# Sheet1.net
KiCad netlist of a schematic drawn in Altium Designer
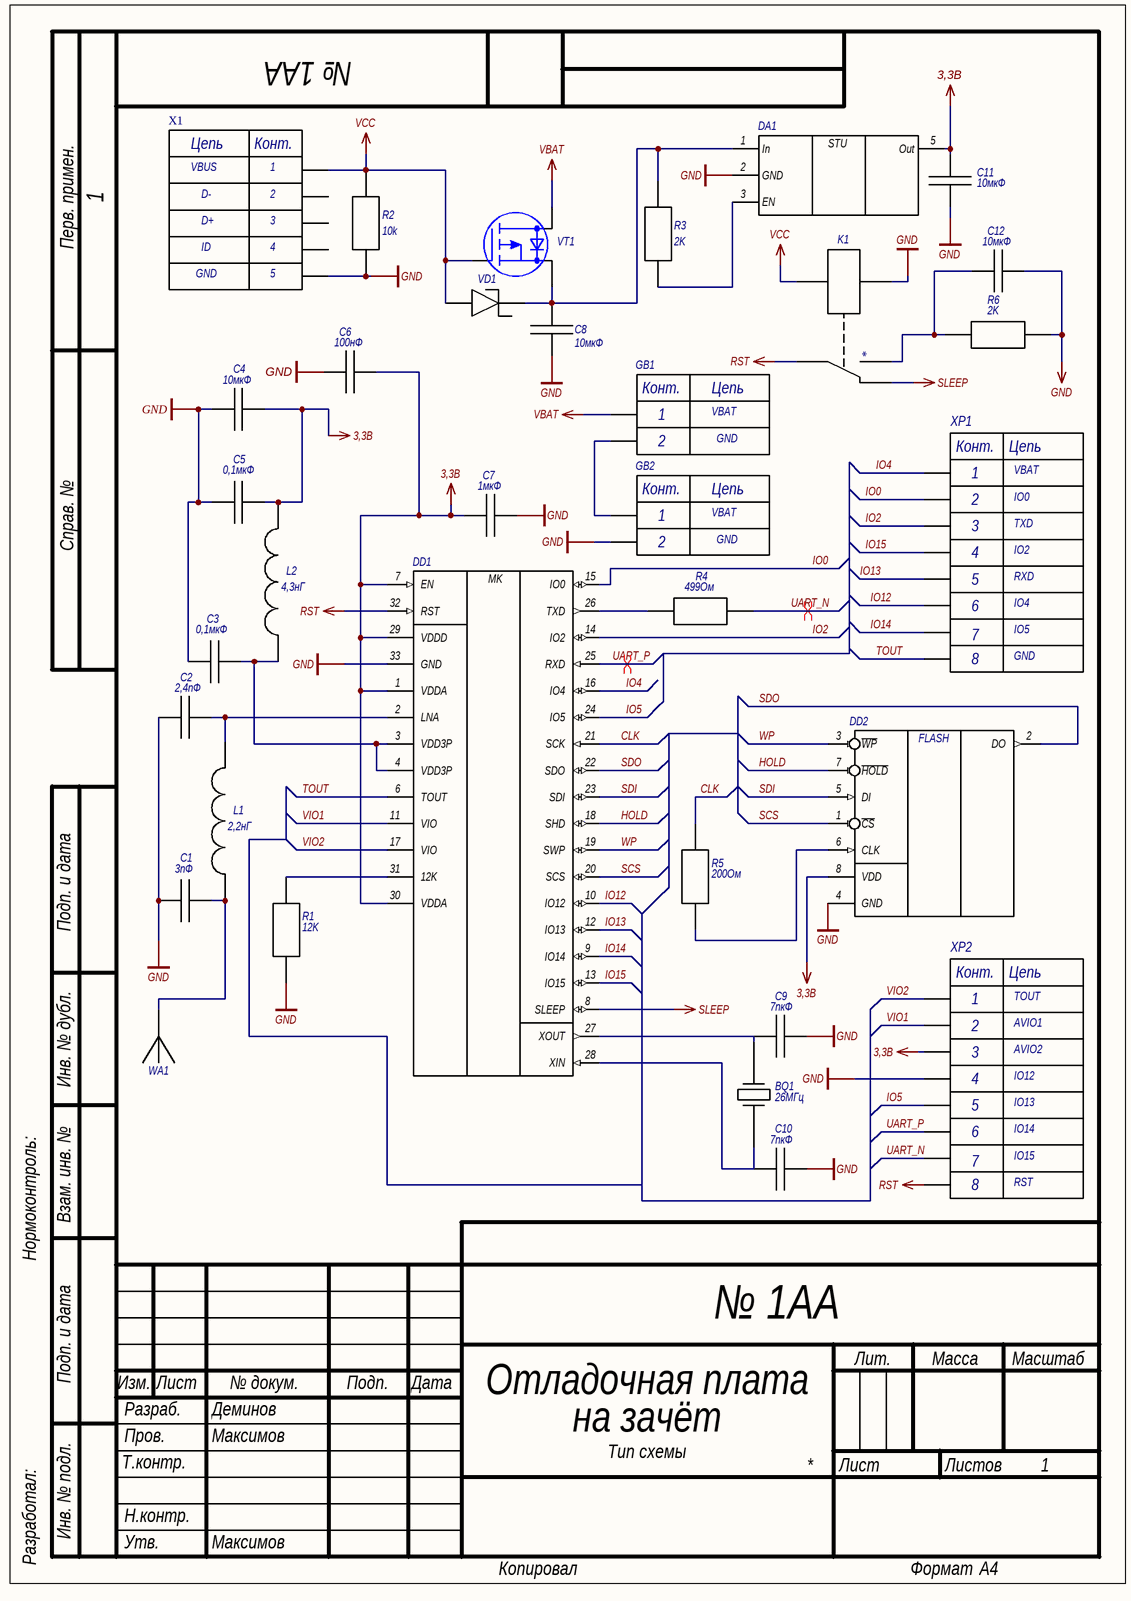
[diagram p0: Sheet1.SchDoc]

(export (version "E")
  (design (tool "Eeschema 10.0.6"))
  (components
    (comp (ref "*") (value "WA1") (libsource (lib "my_lib") (part "ANT GOST")))
    (comp (ref "BQ1")
      (value "26МГц")
      (footprint "SMD02520C4")
      (libsource (lib "my_lib") (part "LBY001XRA001"))
    )
    (comp (ref "C1")
      (value "3пФ")
      (footprint "0201 C0G 7пФ 25В")
      (libsource (lib "my_lib") (part "0201 cap"))
    )
    (comp (ref "C2")
      (value "2,4пФ")
      (footprint "0201 C0G 7пФ 25В")
      (libsource (lib "my_lib") (part "0201 cap"))
    )
    (comp (ref "C3")
      (value "0,1мкФ")
      (footprint "RES 0402")
      (libsource (lib "my_lib") (part "GRM152C80G104KE19D"))
    )
    (comp (ref "C4")
      (value "10мкФ")
      (footprint "FB 0603")
      (libsource (lib "my_lib") (part "GRM188R60G106ME47D"))
    )
    (comp (ref "C5")
      (value "0,1мкФ")
      (footprint "RES 0402")
      (libsource (lib "my_lib") (part "GRM152C80G104KE19D"))
    )
    (comp (ref "C6")
      (value "100нФ")
      (footprint "RES 0402")
      (libsource (lib "my_lib") (part "GRM152C80G104KE19D"))
    )
    (comp (ref "C7")
      (value "1мкФ")
      (footprint "FB 0603")
      (libsource (lib "my_lib") (part "CC0603KRX7R5BB105 1мкФ"))
    )
    (comp (ref "C8")
      (value "10мкФ")
      (footprint "FB 0603")
      (libsource (lib "my_lib") (part "GRM188R60G106ME47D"))
    )
    (comp (ref "C9")
      (value "7пкФ")
      (footprint "0201 C0G 7пФ 25В")
      (libsource (lib "my_lib") (part "0201 cap"))
    )
    (comp (ref "C10")
      (value "7пкФ")
      (footprint "0201 C0G 7пФ 25В")
      (libsource (lib "my_lib") (part "0201 cap"))
    )
    (comp (ref "C11")
      (value "10мкФ")
      (footprint "FB 0603")
      (libsource (lib "my_lib") (part "GRM188R60G106ME47D"))
    )
    (comp (ref "C12")
      (value "10мкФ")
      (footprint "FB 0603")
      (libsource (lib "my_lib") (part "GRM188R60G106ME47D"))
    )
    (comp (ref "DA1") (value "ap2112") (footprint "2112") (libsource (lib "my_lib") (part "ap2112")))
    (comp (ref "DD1") (value "esp8266ex") (footprint "ESP8266") (libsource (lib "my_lib") (part "esp8266ex")))
    (comp (ref "DD2")
      (value "M25P16-VMN6TP")
      (footprint "SOIC-8(3.90мм)")
      (libsource (lib "my_lib") (part "M25P16-VMN6TP"))
    )
    (comp (ref "GB1")
      (value "battery_x2")
      (footprint "Battery_x2AA")
      (libsource (lib "my_lib") (part "battery_x2"))
    )
    (comp (ref "GB2")
      (value "battery_x2")
      (footprint "Battery_x2AA")
      (libsource (lib "my_lib") (part "battery_x2"))
    )
    (comp (ref "K1") (value "gost relay") (footprint "RELE") (libsource (lib "my_lib") (part "gost relay")))
    (comp (ref "L1") (value "2,2нГ") (footprint "FB 0603") (libsource (lib "my_lib") (part "LQW18AN2N2D")))
    (comp (ref "L2")
      (value "4,3нГ")
      (footprint "RES 0402")
      (libsource (lib "my_lib") (part "LQP15MN4N3B02D"))
    )
    (comp (ref "R1") (value "12K") (footprint "RES 0805") (libsource (lib "my_lib") (part "RES 0805")))
    (comp (ref "R2") (value "10k") (footprint "RES 0805") (libsource (lib "my_lib") (part "RES 0805")))
    (comp (ref "R3") (value "2K") (footprint "RES 0805") (libsource (lib "my_lib") (part "RES 0805")))
    (comp (ref "R4") (value "499Ом") (footprint "RES 0805") (libsource (lib "my_lib") (part "RES 0805")))
    (comp (ref "R5") (value "200Ом") (footprint "RES 0805") (libsource (lib "my_lib") (part "RES 0805")))
    (comp (ref "R6") (value "2K") (footprint "RES 0805") (libsource (lib "my_lib") (part "RES 0805")))
    (comp (ref "VD1") (value "~") (footprint "MBR120") (libsource (lib "my_lib") (part "MBR120")))
    (comp (ref "VT1")
      (value "~")
      (footprint "SOT23-3")
      (description "N-MOSFET")
      (fields (field (name "PART NUMBER") "SI2325DS-T1-GE3") (field (name "MANUFACTURER") "IXYS"))
      (libsource (lib "MOP44") (part "P-MOSFET"))
    )
    (comp (ref "X1")
      (value "usb_micro")
      (footprint "USB_mini_B")
      (libsource (lib "my_lib") (part "usb_micro"))
    )
    (comp (ref "XP1")
      (value "PLD-8")
      (footprint "PLD-8")
      (description "PLD connector")
      (fields (field (name "MANUFACTURER") "NONAME"))
      (libsource (lib "my_lib") (part "PLD-8"))
    )
    (comp (ref "XP2")
      (value "PLD-8")
      (footprint "PLD-8")
      (description "PLD connector")
      (fields (field (name "MANUFACTURER") "NONAME"))
      (libsource (lib "my_lib") (part "PLD-8"))
    )
  )
  (nets
    (net (code "1") (name "/CLK") (class "Default")
      (node (ref "DD1") (pin "21") (pinfunction "SCK_21") (pintype "input"))
      (node (ref "R5") (pin "1") (pinfunction "1_1") (pintype "passive"))
    )
    (net (code "2") (name "/HOLD") (class "Default")
      (node (ref "DD1") (pin "18") (pinfunction "SHD_18") (pintype "bidirectional"))
      (node (ref "DD2") (pin "7") (pinfunction "~{HOLD}_7") (pintype "input"))
    )
    (net (code "3") (name "/IO0") (class "Default")
      (node (ref "DD1") (pin "15") (pinfunction "IO0_15") (pintype "bidirectional"))
      (node (ref "XP1") (pin "2") (pinfunction "2_2") (pintype "passive"))
    )
    (net (code "4") (name "/IO2") (class "Default")
      (node (ref "DD1") (pin "14") (pinfunction "IO2_14") (pintype "bidirectional"))
      (node (ref "XP1") (pin "3") (pinfunction "3_3") (pintype "passive"))
    )
    (net (code "5") (name "/IO4") (class "Default")
      (node (ref "DD1") (pin "16") (pinfunction "IO4_16") (pintype "bidirectional"))
      (node (ref "XP1") (pin "1") (pinfunction "1_1") (pintype "passive"))
    )
    (net (code "6") (name "/IO5") (class "Default")
      (node (ref "DD1") (pin "24") (pinfunction "IO5_24") (pintype "bidirectional"))
      (node (ref "XP2") (pin "5") (pinfunction "5_5") (pintype "passive"))
    )
    (net (code "7") (name "/IO12") (class "Default")
      (node (ref "DD1") (pin "10") (pinfunction "IO12_10") (pintype "bidirectional"))
      (node (ref "XP1") (pin "6") (pinfunction "6_6") (pintype "passive"))
    )
    (net (code "8") (name "/IO13") (class "Default")
      (node (ref "DD1") (pin "12") (pinfunction "IO13_12") (pintype "bidirectional"))
      (node (ref "XP1") (pin "5") (pinfunction "5_5") (pintype "passive"))
    )
    (net (code "9") (name "/IO14") (class "Default")
      (node (ref "DD1") (pin "9") (pinfunction "IO14_9") (pintype "bidirectional"))
      (node (ref "XP1") (pin "7") (pinfunction "7_7") (pintype "passive"))
    )
    (net (code "10") (name "/IO15") (class "Default")
      (node (ref "DD1") (pin "13") (pinfunction "IO15_13") (pintype "bidirectional"))
      (node (ref "XP1") (pin "4") (pinfunction "4_4") (pintype "passive"))
    )
    (net (code "11") (name "/SCS") (class "Default")
      (node (ref "DD1") (pin "20") (pinfunction "SCS_20") (pintype "bidirectional"))
      (node (ref "DD2") (pin "1") (pinfunction "~{CS}_1") (pintype "input"))
    )
    (net (code "12") (name "/SDI") (class "Default")
      (node (ref "DD1") (pin "23") (pinfunction "SDI_23") (pintype "bidirectional"))
      (node (ref "DD2") (pin "5") (pinfunction "DI_5") (pintype "input"))
    )
    (net (code "13") (name "/SDO") (class "Default")
      (node (ref "DD1") (pin "22") (pinfunction "SDO_22") (pintype "bidirectional"))
      (node (ref "DD2") (pin "2") (pinfunction "DO_2") (pintype "output"))
    )
    (net (code "14") (name "/TOUT") (class "Default")
      (node (ref "DD1") (pin "6") (pinfunction "TOUT_6") (pintype "power_in"))
      (node (ref "XP1") (pin "8") (pinfunction "8_8") (pintype "passive"))
    )
    (net (code "15") (name "/UART_N") (class "Default")
      (node (ref "R4") (pin "2") (pinfunction "2_2") (pintype "passive"))
      (node (ref "XP2") (pin "7") (pinfunction "7_7") (pintype "passive"))
    )
    (net (code "16") (name "/UART_P") (class "Default")
      (node (ref "DD1") (pin "25") (pinfunction "RXD_25") (pintype "input"))
      (node (ref "XP2") (pin "6") (pinfunction "6_6") (pintype "passive"))
    )
    (net (code "17") (name "/VIO1") (class "Default")
      (node (ref "DD1") (pin "11") (pinfunction "VIO_11") (pintype "power_in"))
      (node (ref "XP2") (pin "2") (pinfunction "2_2") (pintype "passive"))
    )
    (net (code "18") (name "/VIO2") (class "Default")
      (node (ref "DD1") (pin "17") (pinfunction "VIO_17") (pintype "power_in"))
      (node (ref "XP2") (pin "1") (pinfunction "1_1") (pintype "passive"))
    )
    (net (code "19") (name "/WP") (class "Default")
      (node (ref "DD1") (pin "19") (pinfunction "SWP_19") (pintype "bidirectional"))
      (node (ref "DD2") (pin "3") (pinfunction "~{WP}_3") (pintype "input"))
    )
    (net (code "20") (name "3,3B") (class "Default")
      (node (ref "C11") (pin "2") (pinfunction "2_2") (pintype "passive"))
      (node (ref "C4") (pin "2") (pinfunction "2_2") (pintype "passive"))
      (node (ref "C5") (pin "1") (pinfunction "1_1") (pintype "passive"))
      (node (ref "C6") (pin "1") (pinfunction "1_1") (pintype "passive"))
      (node (ref "C7") (pin "1") (pinfunction "1_1") (pintype "passive"))
      (node (ref "DA1") (pin "5") (pinfunction "Out_5") (pintype "passive"))
      (node (ref "DD1") (pin "1") (pinfunction "VDDA_1") (pintype "power_in"))
      (node (ref "DD1") (pin "29") (pinfunction "VDDD_29") (pintype "power_in"))
      (node (ref "DD1") (pin "30") (pinfunction "VDDA_30") (pintype "power_in"))
      (node (ref "DD1") (pin "7") (pinfunction "EN_7") (pintype "input"))
      (node (ref "DD2") (pin "8") (pinfunction "VDD_8") (pintype "power_in"))
      (node (ref "L2") (pin "2") (pinfunction "2_2") (pintype "passive"))
      (node (ref "XP2") (pin "3") (pinfunction "3_3") (pintype "passive"))
    )
    (net (code "21") (name "GND") (class "Default")
      (node (ref "C1") (pin "2") (pinfunction "2_2") (pintype "passive"))
      (node (ref "C10") (pin "1") (pinfunction "1_1") (pintype "passive"))
      (node (ref "C11") (pin "1") (pinfunction "1_1") (pintype "passive"))
      (node (ref "C12") (pin "1") (pinfunction "1_1") (pintype "passive"))
      (node (ref "C2") (pin "2") (pinfunction "2_2") (pintype "passive"))
      (node (ref "C3") (pin "2") (pinfunction "2_2") (pintype "passive"))
      (node (ref "C4") (pin "1") (pinfunction "1_1") (pintype "passive"))
      (node (ref "C5") (pin "2") (pinfunction "2_2") (pintype "passive"))
      (node (ref "C6") (pin "2") (pinfunction "2_2") (pintype "passive"))
      (node (ref "C7") (pin "2") (pinfunction "2_2") (pintype "passive"))
      (node (ref "C8") (pin "1") (pinfunction "1_1") (pintype "passive"))
      (node (ref "C9") (pin "1") (pinfunction "1_1") (pintype "passive"))
      (node (ref "DA1") (pin "2") (pinfunction "GND_2") (pintype "passive"))
      (node (ref "DD1") (pin "33") (pinfunction "GND_33") (pintype "power_in"))
      (node (ref "DD2") (pin "4") (pinfunction "GND_4") (pintype "power_in"))
      (node (ref "GB2") (pin "2") (pinfunction "2_2") (pintype "passive"))
      (node (ref "K1") (pin "8") (pinfunction "26_8") (pintype "passive"))
      (node (ref "R1") (pin "2") (pinfunction "2_2") (pintype "passive"))
      (node (ref "R2") (pin "2") (pinfunction "2_2") (pintype "passive"))
      (node (ref "R6") (pin "1") (pinfunction "1_1") (pintype "passive"))
      (node (ref "X1") (pin "5") (pinfunction "5_5") (pintype "passive"))
      (node (ref "XP2") (pin "4") (pinfunction "4_4") (pintype "passive"))
    )
    (net (code "22") (name "Net-(*-27)") (class "Default")
      (node (ref "*") (pin "IN") (pinfunction "27_IN") (pintype "passive"))
      (node (ref "C1") (pin "1") (pinfunction "1_1") (pintype "passive"))
      (node (ref "L1") (pin "1") (pinfunction "1_1") (pintype "passive"))
    )
    (net (code "23") (name "Net-(C3-Pad1)") (class "Default")
      (node (ref "C3") (pin "1") (pinfunction "1_1") (pintype "passive"))
      (node (ref "DD1") (pin "3") (pinfunction "VDD3P_3") (pintype "power_in"))
      (node (ref "DD1") (pin "4") (pinfunction "VDD3P_4") (pintype "power_in"))
      (node (ref "L2") (pin "1") (pinfunction "1_1") (pintype "passive"))
    )
    (net (code "24") (name "Net-(C12-Pad2)") (class "Default")
      (node (ref "C12") (pin "2") (pinfunction "2_2") (pintype "passive"))
      (node (ref "K1") (pin "3") (pinfunction "26_3") (pintype "passive"))
      (node (ref "R6") (pin "2") (pinfunction "2_2") (pintype "passive"))
    )
    (net (code "25") (name "Net-(DA1-EN)") (class "Default")
      (node (ref "DA1") (pin "3") (pinfunction "EN_3") (pintype "passive"))
      (node (ref "R3") (pin "1") (pinfunction "1_1") (pintype "passive"))
    )
    (net (code "26") (name "Net-(DA1-In)") (class "Default")
      (node (ref "C8") (pin "2") (pinfunction "2_2") (pintype "passive"))
      (node (ref "DA1") (pin "1") (pinfunction "In_1") (pintype "passive"))
      (node (ref "R3") (pin "2") (pinfunction "2_2") (pintype "passive"))
      (node (ref "VD1") (pin "1") (pinfunction "1_1") (pintype "passive"))
      (node (ref "VT1") (pin "3") (pinfunction "S_3") (pintype "passive"))
    )
    (net (code "27") (name "Net-(DD1-12K)") (class "Default")
      (node (ref "DD1") (pin "31") (pinfunction "12K_31") (pintype "power_in"))
      (node (ref "R1") (pin "1") (pinfunction "1_1") (pintype "passive"))
    )
    (net (code "28") (name "Net-(DD1-LNA)") (class "Default")
      (node (ref "C2") (pin "1") (pinfunction "1_1") (pintype "passive"))
      (node (ref "DD1") (pin "2") (pinfunction "LNA_2") (pintype "power_in"))
      (node (ref "L1") (pin "2") (pinfunction "2_2") (pintype "passive"))
    )
    (net (code "29") (name "Net-(DD1-TXD)") (class "Default")
      (node (ref "DD1") (pin "26") (pinfunction "TXD_26") (pintype "output"))
      (node (ref "R4") (pin "1") (pinfunction "1_1") (pintype "passive"))
    )
    (net (code "30") (name "Net-(DD1-XIN)") (class "Default")
      (node (ref "BQ1") (pin "1") (pinfunction "1_1") (pintype "passive"))
      (node (ref "C10") (pin "2") (pinfunction "2_2") (pintype "passive"))
      (node (ref "DD1") (pin "28") (pinfunction "XIN_28") (pintype "input"))
    )
    (net (code "31") (name "Net-(DD1-XOUT)") (class "Default")
      (node (ref "BQ1") (pin "3") (pinfunction "3_3") (pintype "passive"))
      (node (ref "C9") (pin "2") (pinfunction "2_2") (pintype "passive"))
      (node (ref "DD1") (pin "27") (pinfunction "XOUT_27") (pintype "output"))
    )
    (net (code "32") (name "Net-(DD2-CLK)") (class "Default")
      (node (ref "DD2") (pin "6") (pinfunction "CLK_6") (pintype "input"))
      (node (ref "R5") (pin "2") (pinfunction "2_2") (pintype "passive"))
    )
    (net (code "33") (name "Net-(GB1-Pad2)") (class "Default")
      (node (ref "GB1") (pin "2") (pinfunction "2_2") (pintype "passive"))
      (node (ref "GB2") (pin "1") (pinfunction "1_1") (pintype "passive"))
    )
    (net (code "34") (name "RST") (class "Default")
      (node (ref "DD1") (pin "32") (pinfunction "RST_32") (pintype "input"))
      (node (ref "K1") (pin "3") (pinfunction "26_3") (pintype "passive"))
      (node (ref "XP2") (pin "8") (pinfunction "8_8") (pintype "passive"))
    )
    (net (code "35") (name "SLEEP") (class "Default")
      (node (ref "DD1") (pin "8") (pinfunction "SLEEP_8") (pintype "bidirectional"))
      (node (ref "K1") (pin "4") (pinfunction "26_4") (pintype "passive"))
    )
    (net (code "36") (name "VBAT") (class "Default")
      (node (ref "GB1") (pin "1") (pinfunction "1_1") (pintype "passive"))
      (node (ref "VT1") (pin "2") (pinfunction "D_2") (pintype "passive"))
    )
    (net (code "37") (name "VCC") (class "Default")
      (node (ref "K1") (pin "1") (pinfunction "26_1") (pintype "passive"))
      (node (ref "R2") (pin "1") (pinfunction "1_1") (pintype "passive"))
      (node (ref "VD1") (pin "2") (pinfunction "2_2") (pintype "passive"))
      (node (ref "VT1") (pin "1") (pinfunction "G_1") (pintype "passive"))
      (node (ref "X1") (pin "1") (pinfunction "1_1") (pintype "passive"))
    )
    (net (code "38") (name "unconnected-(X1-Pad2)") (class "Default")
      (node (ref "X1") (pin "2") (pinfunction "2_2") (pintype "passive"))
    )
    (net (code "39") (name "unconnected-(X1-Pad3)") (class "Default")
      (node (ref "X1") (pin "3") (pinfunction "3_3") (pintype "passive"))
    )
    (net (code "40") (name "unconnected-(X1-Pad4)") (class "Default")
      (node (ref "X1") (pin "4") (pinfunction "4_4") (pintype "passive"))
    )
  )
)
